# Cansat2019_3279_Container_v05.net
KiCad netlist of a schematic drawn in EAGLE
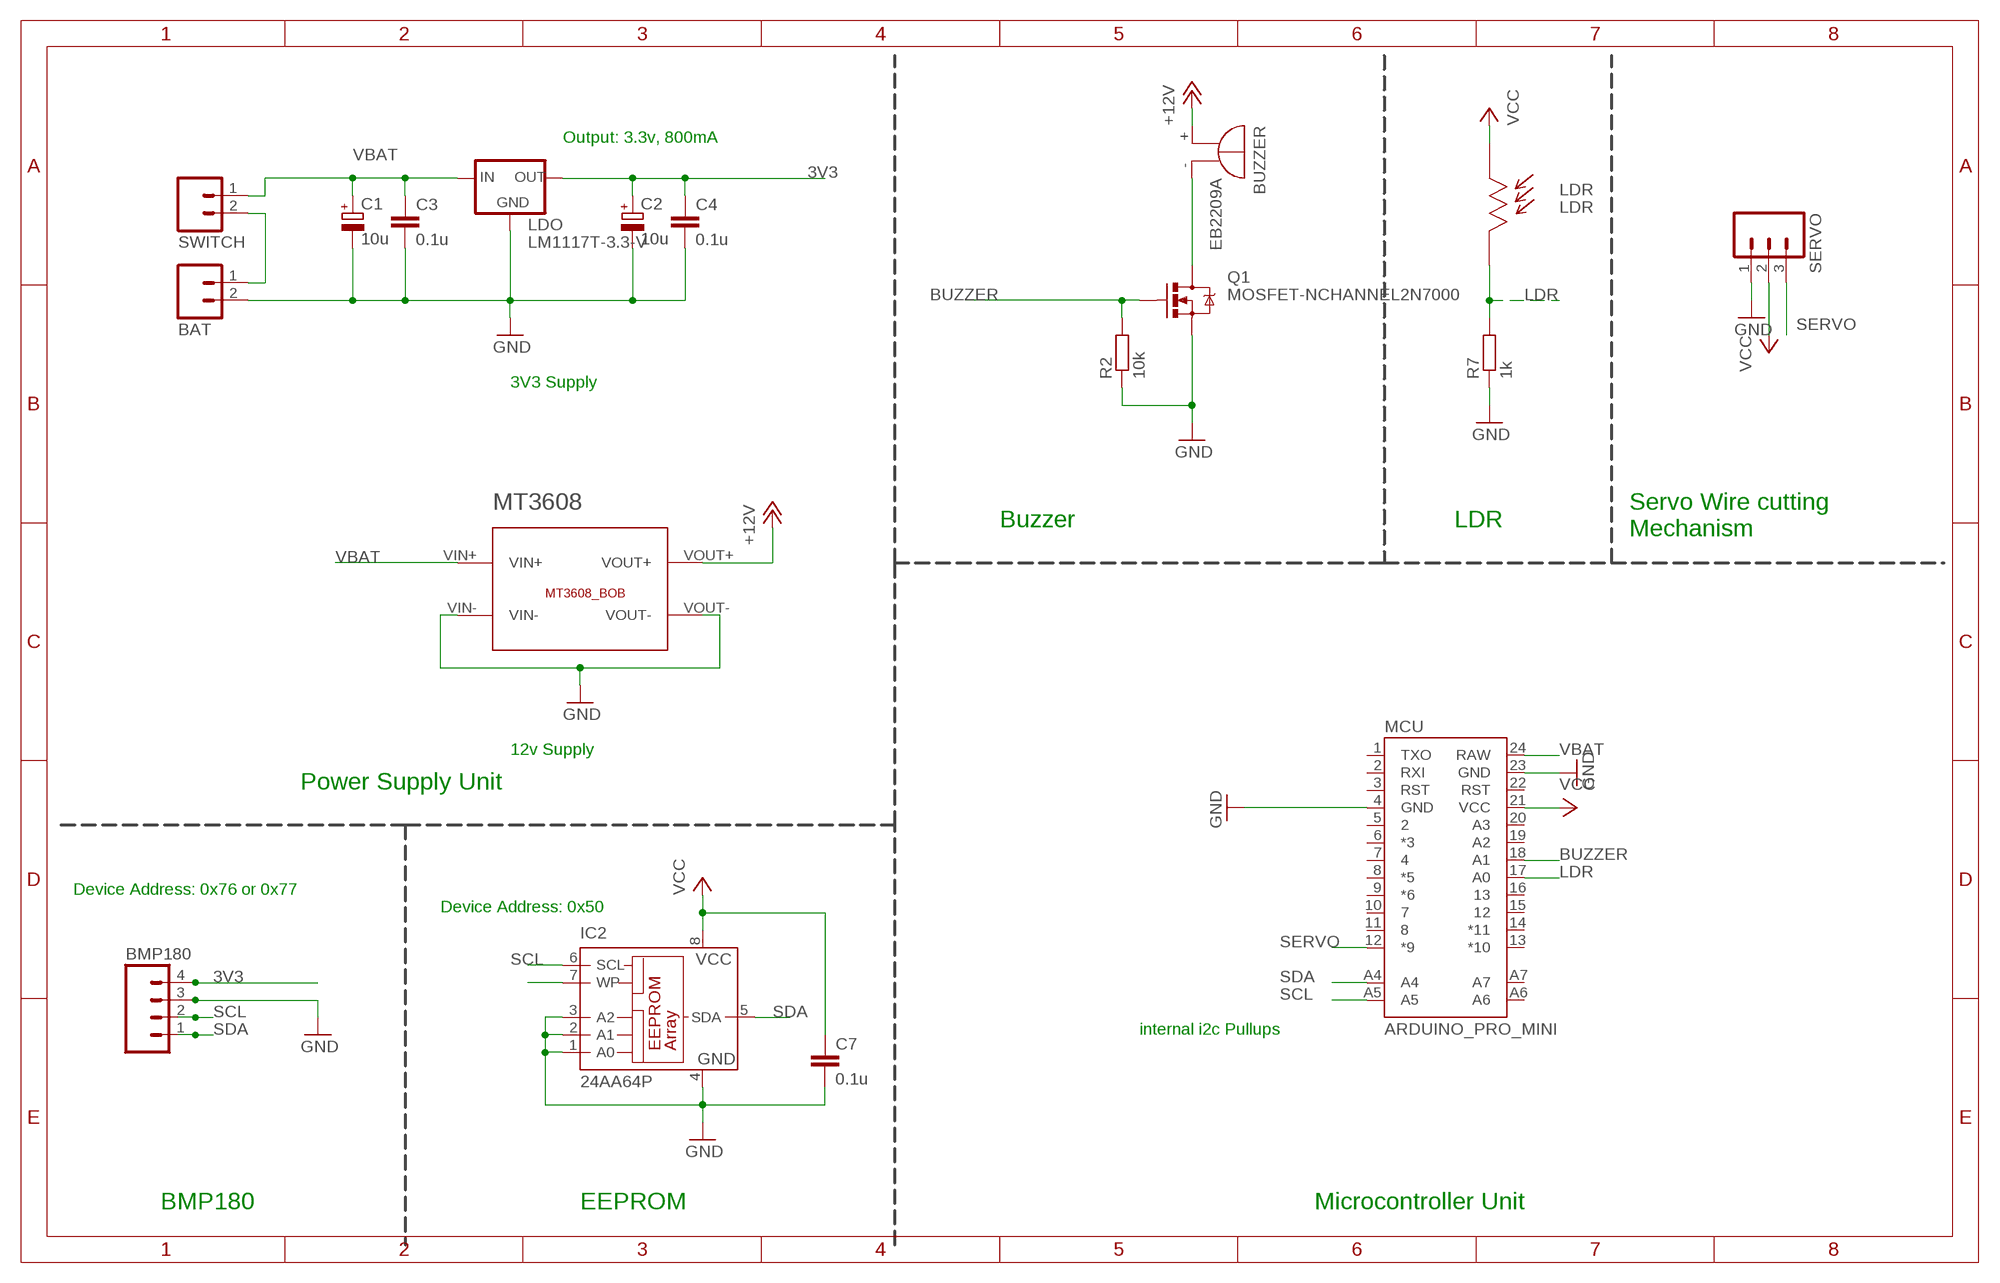
[diagram p0: schematic, sheet 1]

(export (version "E")
  (design (tool "Eeschema 10.0.6"))
  (components
    (comp (ref "BAT")
      (value "M02")
      (footprint "eagle-import:02P")
      (libsource (lib "eagle-import") (part "M02"))
    )
    (comp (ref "BMP180")
      (value "M04")
      (footprint "eagle-import:04P")
      (libsource (lib "eagle-import") (part "M04"))
    )
    (comp (ref "BUZZER")
      (value "EB2209A")
      (footprint "eagle-import:EB2209A")
      (libsource (lib "eagle-import") (part "EB2209A"))
    )
    (comp (ref "C1")
      (value "10u")
      (footprint "eagle-import:E2,5-6")
      (libsource (lib "eagle-import") (part "CPOL-EUE2.5-6"))
    )
    (comp (ref "C2")
      (value "10u")
      (footprint "eagle-import:E2,5-6")
      (libsource (lib "eagle-import") (part "CPOL-EUE2.5-6"))
    )
    (comp (ref "C3")
      (value "0.1u")
      (footprint "eagle-import:C025-025X050")
      (libsource (lib "eagle-import") (part "C-EU025-025X050"))
    )
    (comp (ref "C4")
      (value "0.1u")
      (footprint "eagle-import:C025-025X050")
      (libsource (lib "eagle-import") (part "C-EU025-025X050"))
    )
    (comp (ref "C7")
      (value "0.1u")
      (footprint "eagle-import:C025-025X050")
      (libsource (lib "eagle-import") (part "C-EU025-025X050"))
    )
    (comp (ref "IC2")
      (value "24AA64P")
      (footprint "eagle-import:DIL8")
      (fields (field (name "MF") "MICROCHIP") (field (name "MPN") "24AA64-I/P"))
      (libsource (lib "eagle-import") (part "24PAA64"))
    )
    (comp (ref "LDO")
      (value "LM1117T-3.3-V")
      (footprint "eagle-import:TO220V")
      (libsource (lib "eagle-import") (part "LM1117T--V3.3"))
    )
    (comp (ref "LDR")
      (value "LDR")
      (footprint "eagle-import:LDR-5MM")
      (libsource (lib "eagle-import") (part "LDR"))
    )
    (comp (ref "MCU")
      (value "ARDUINO_PRO_MINI")
      (footprint "eagle-import:ARDUINO_PRO_MINI")
      (libsource (lib "eagle-import") (part "ARDUINO_PRO_MINI"))
    )
    (comp (ref "MT3608")
      (value "MT3608_BOB")
      (footprint "eagle-import:MT3608_BOB")
      (libsource (lib "eagle-import") (part "MT3608_BOB"))
    )
    (comp (ref "Q1")
      (value "MOSFET-NCHANNEL2N7000")
      (footprint "eagle-import:TO-92")
      (libsource (lib "eagle-import") (part "MOSFET-NCHANNEL2N7000"))
    )
    (comp (ref "R2")
      (value "10k")
      (footprint "eagle-import:0204_7")
      (libsource (lib "eagle-import") (part "R-EU_0204/7"))
    )
    (comp (ref "R7")
      (value "1k")
      (footprint "eagle-import:0204_7")
      (libsource (lib "eagle-import") (part "R-EU_0204/7"))
    )
    (comp (ref "SERVO")
      (value "M03")
      (footprint "eagle-import:03P")
      (libsource (lib "eagle-import") (part "M03"))
    )
    (comp (ref "SWITCH")
      (value "M02")
      (footprint "eagle-import:02P")
      (libsource (lib "eagle-import") (part "M02"))
    )
  )
  (nets
    (net (code "1") (name "+12V") (class "Default")
      (node (ref "BUZZER") (pin "+") (pinfunction "+_+") (pintype "passive"))
      (node (ref "MT3608") (pin "VOUT+") (pinfunction "VOUT+_VOUT+") (pintype "bidirectional"))
    )
    (net (code "2") (name "/3V3") (class "Default")
      (node (ref "BMP180") (pin "4") (pinfunction "4_4") (pintype "passive"))
      (node (ref "C2") (pin "+") (pinfunction "+_+") (pintype "passive"))
      (node (ref "C4") (pin "1") (pinfunction "1_1") (pintype "passive"))
      (node (ref "LDO") (pin "2") (pinfunction "OUT_2") (pintype "passive"))
    )
    (net (code "3") (name "/BUZZER") (class "Default")
      (node (ref "MCU") (pin "18") (pinfunction "A1_18") (pintype "bidirectional"))
      (node (ref "Q1") (pin "2") (pinfunction "G_2") (pintype "passive"))
      (node (ref "R2") (pin "2") (pinfunction "2_2") (pintype "passive"))
    )
    (net (code "4") (name "/LDR") (class "Default")
      (node (ref "LDR") (pin "P$2") (pinfunction "P$2_P$2") (pintype "bidirectional"))
      (node (ref "MCU") (pin "17") (pinfunction "A0_17") (pintype "bidirectional"))
      (node (ref "R7") (pin "2") (pinfunction "2_2") (pintype "passive"))
    )
    (net (code "5") (name "/SCL") (class "Default")
      (node (ref "BMP180") (pin "2") (pinfunction "2_2") (pintype "passive"))
      (node (ref "IC2") (pin "6") (pinfunction "SCL_6") (pintype "input"))
      (node (ref "MCU") (pin "A5") (pinfunction "A5_A5") (pintype "bidirectional"))
    )
    (net (code "6") (name "/SDA") (class "Default")
      (node (ref "BMP180") (pin "1") (pinfunction "1_1") (pintype "passive"))
      (node (ref "IC2") (pin "5") (pinfunction "SDA_5") (pintype "bidirectional"))
      (node (ref "MCU") (pin "A4") (pinfunction "A4_A4") (pintype "bidirectional"))
    )
    (net (code "7") (name "/SERVO") (class "Default")
      (node (ref "MCU") (pin "12") (pinfunction "*9_12") (pintype "bidirectional"))
      (node (ref "SERVO") (pin "3") (pinfunction "3_3") (pintype "passive"))
    )
    (net (code "8") (name "/VBAT") (class "Default")
      (node (ref "C1") (pin "+") (pinfunction "+_+") (pintype "passive"))
      (node (ref "C3") (pin "1") (pinfunction "1_1") (pintype "passive"))
      (node (ref "LDO") (pin "3") (pinfunction "IN_3") (pintype "input"))
      (node (ref "MCU") (pin "24") (pinfunction "RAW_24") (pintype "bidirectional"))
      (node (ref "MT3608") (pin "VIN+") (pinfunction "VIN+_VIN+") (pintype "bidirectional"))
      (node (ref "SWITCH") (pin "1") (pinfunction "1_1") (pintype "passive"))
    )
    (net (code "9") (name "GND") (class "Default")
      (node (ref "BAT") (pin "2") (pinfunction "2_2") (pintype "passive"))
      (node (ref "BMP180") (pin "3") (pinfunction "3_3") (pintype "passive"))
      (node (ref "C1") (pin "-") (pinfunction "-_-") (pintype "passive"))
      (node (ref "C2") (pin "-") (pinfunction "-_-") (pintype "passive"))
      (node (ref "C3") (pin "2") (pinfunction "2_2") (pintype "passive"))
      (node (ref "C4") (pin "2") (pinfunction "2_2") (pintype "passive"))
      (node (ref "C7") (pin "2") (pinfunction "2_2") (pintype "passive"))
      (node (ref "IC2") (pin "1") (pinfunction "A0_1") (pintype "input"))
      (node (ref "IC2") (pin "2") (pinfunction "A1_2") (pintype "input"))
      (node (ref "IC2") (pin "3") (pinfunction "A2_3") (pintype "input"))
      (node (ref "IC2") (pin "4") (pinfunction "GND_4") (pintype "power_in"))
      (node (ref "LDO") (pin "1") (pinfunction "GND_1") (pintype "input"))
      (node (ref "MCU") (pin "23") (pinfunction "GND_23") (pintype "bidirectional"))
      (node (ref "MCU") (pin "4") (pinfunction "GND_4") (pintype "bidirectional"))
      (node (ref "MT3608") (pin "VIN-") (pinfunction "VIN-_VIN-") (pintype "bidirectional"))
      (node (ref "MT3608") (pin "VOUT-") (pinfunction "VOUT-_VOUT-") (pintype "bidirectional"))
      (node (ref "Q1") (pin "1") (pinfunction "S_1") (pintype "passive"))
      (node (ref "R2") (pin "1") (pinfunction "1_1") (pintype "passive"))
      (node (ref "R7") (pin "1") (pinfunction "1_1") (pintype "passive"))
      (node (ref "SERVO") (pin "1") (pinfunction "1_1") (pintype "passive"))
    )
    (net (code "10") (name "Net-(BAT-Pad1)") (class "Default")
      (node (ref "BAT") (pin "1") (pinfunction "1_1") (pintype "passive"))
      (node (ref "SWITCH") (pin "2") (pinfunction "2_2") (pintype "passive"))
    )
    (net (code "11") (name "Net-(Q1-D)") (class "Default")
      (node (ref "BUZZER") (pin "-") (pinfunction "-_-") (pintype "passive"))
      (node (ref "Q1") (pin "3") (pinfunction "D_3") (pintype "passive"))
    )
    (net (code "12") (name "VCC") (class "Default")
      (node (ref "C7") (pin "1") (pinfunction "1_1") (pintype "passive"))
      (node (ref "IC2") (pin "8") (pinfunction "VCC_8") (pintype "power_in"))
      (node (ref "LDR") (pin "P$1") (pinfunction "P$1_P$1") (pintype "bidirectional"))
      (node (ref "MCU") (pin "21") (pinfunction "VCC_21") (pintype "bidirectional"))
      (node (ref "SERVO") (pin "2") (pinfunction "2_2") (pintype "passive"))
    )
    (net (code "13") (name "unconnected-(IC2-WP-Pad7)") (class "Default")
      (node (ref "IC2") (pin "7") (pinfunction "WP_7") (pintype "input"))
    )
    (net (code "14") (name "unconnected-(MCU-*3-Pad6)") (class "Default")
      (node (ref "MCU") (pin "6") (pinfunction "*3_6") (pintype "bidirectional"))
    )
    (net (code "15") (name "unconnected-(MCU-*5-Pad8)") (class "Default")
      (node (ref "MCU") (pin "8") (pinfunction "*5_8") (pintype "bidirectional"))
    )
    (net (code "16") (name "unconnected-(MCU-*6-Pad9)") (class "Default")
      (node (ref "MCU") (pin "9") (pinfunction "*6_9") (pintype "bidirectional"))
    )
    (net (code "17") (name "unconnected-(MCU-*10-Pad13)") (class "Default")
      (node (ref "MCU") (pin "13") (pinfunction "*10_13") (pintype "bidirectional"))
    )
    (net (code "18") (name "unconnected-(MCU-*11-Pad14)") (class "Default")
      (node (ref "MCU") (pin "14") (pinfunction "*11_14") (pintype "bidirectional"))
    )
    (net (code "19") (name "unconnected-(MCU-2-Pad5)") (class "Default")
      (node (ref "MCU") (pin "5") (pinfunction "2_5") (pintype "bidirectional"))
    )
    (net (code "20") (name "unconnected-(MCU-4-Pad7)") (class "Default")
      (node (ref "MCU") (pin "7") (pinfunction "4_7") (pintype "bidirectional"))
    )
    (net (code "21") (name "unconnected-(MCU-7-Pad10)") (class "Default")
      (node (ref "MCU") (pin "10") (pinfunction "7_10") (pintype "bidirectional"))
    )
    (net (code "22") (name "unconnected-(MCU-8-Pad11)") (class "Default")
      (node (ref "MCU") (pin "11") (pinfunction "8_11") (pintype "bidirectional"))
    )
    (net (code "23") (name "unconnected-(MCU-12-Pad15)") (class "Default")
      (node (ref "MCU") (pin "15") (pinfunction "12_15") (pintype "bidirectional"))
    )
    (net (code "24") (name "unconnected-(MCU-13-Pad16)") (class "Default")
      (node (ref "MCU") (pin "16") (pinfunction "13_16") (pintype "bidirectional"))
    )
    (net (code "25") (name "unconnected-(MCU-A2-Pad19)") (class "Default")
      (node (ref "MCU") (pin "19") (pinfunction "A2_19") (pintype "bidirectional"))
    )
    (net (code "26") (name "unconnected-(MCU-A3-Pad20)") (class "Default")
      (node (ref "MCU") (pin "20") (pinfunction "A3_20") (pintype "bidirectional"))
    )
    (net (code "27") (name "unconnected-(MCU-PadA6)") (class "Default")
      (node (ref "MCU") (pin "A6") (pinfunction "A6_A6") (pintype "bidirectional"))
    )
    (net (code "28") (name "unconnected-(MCU-PadA7)") (class "Default")
      (node (ref "MCU") (pin "A7") (pinfunction "A7_A7") (pintype "bidirectional"))
    )
    (net (code "29") (name "unconnected-(MCU-RST-Pad3)") (class "Default")
      (node (ref "MCU") (pin "3") (pinfunction "RST_3") (pintype "bidirectional"))
    )
    (net (code "30") (name "unconnected-(MCU-RST-Pad22)") (class "Default")
      (node (ref "MCU") (pin "22") (pinfunction "RST_22") (pintype "bidirectional"))
    )
    (net (code "31") (name "unconnected-(MCU-RXI-Pad2)") (class "Default")
      (node (ref "MCU") (pin "2") (pinfunction "RXI_2") (pintype "bidirectional"))
    )
    (net (code "32") (name "unconnected-(MCU-TXO-Pad1)") (class "Default")
      (node (ref "MCU") (pin "1") (pinfunction "TXO_1") (pintype "bidirectional"))
    )
  )
)
